# PR9017.net
KiCad netlist of a schematic drawn in EAGLE
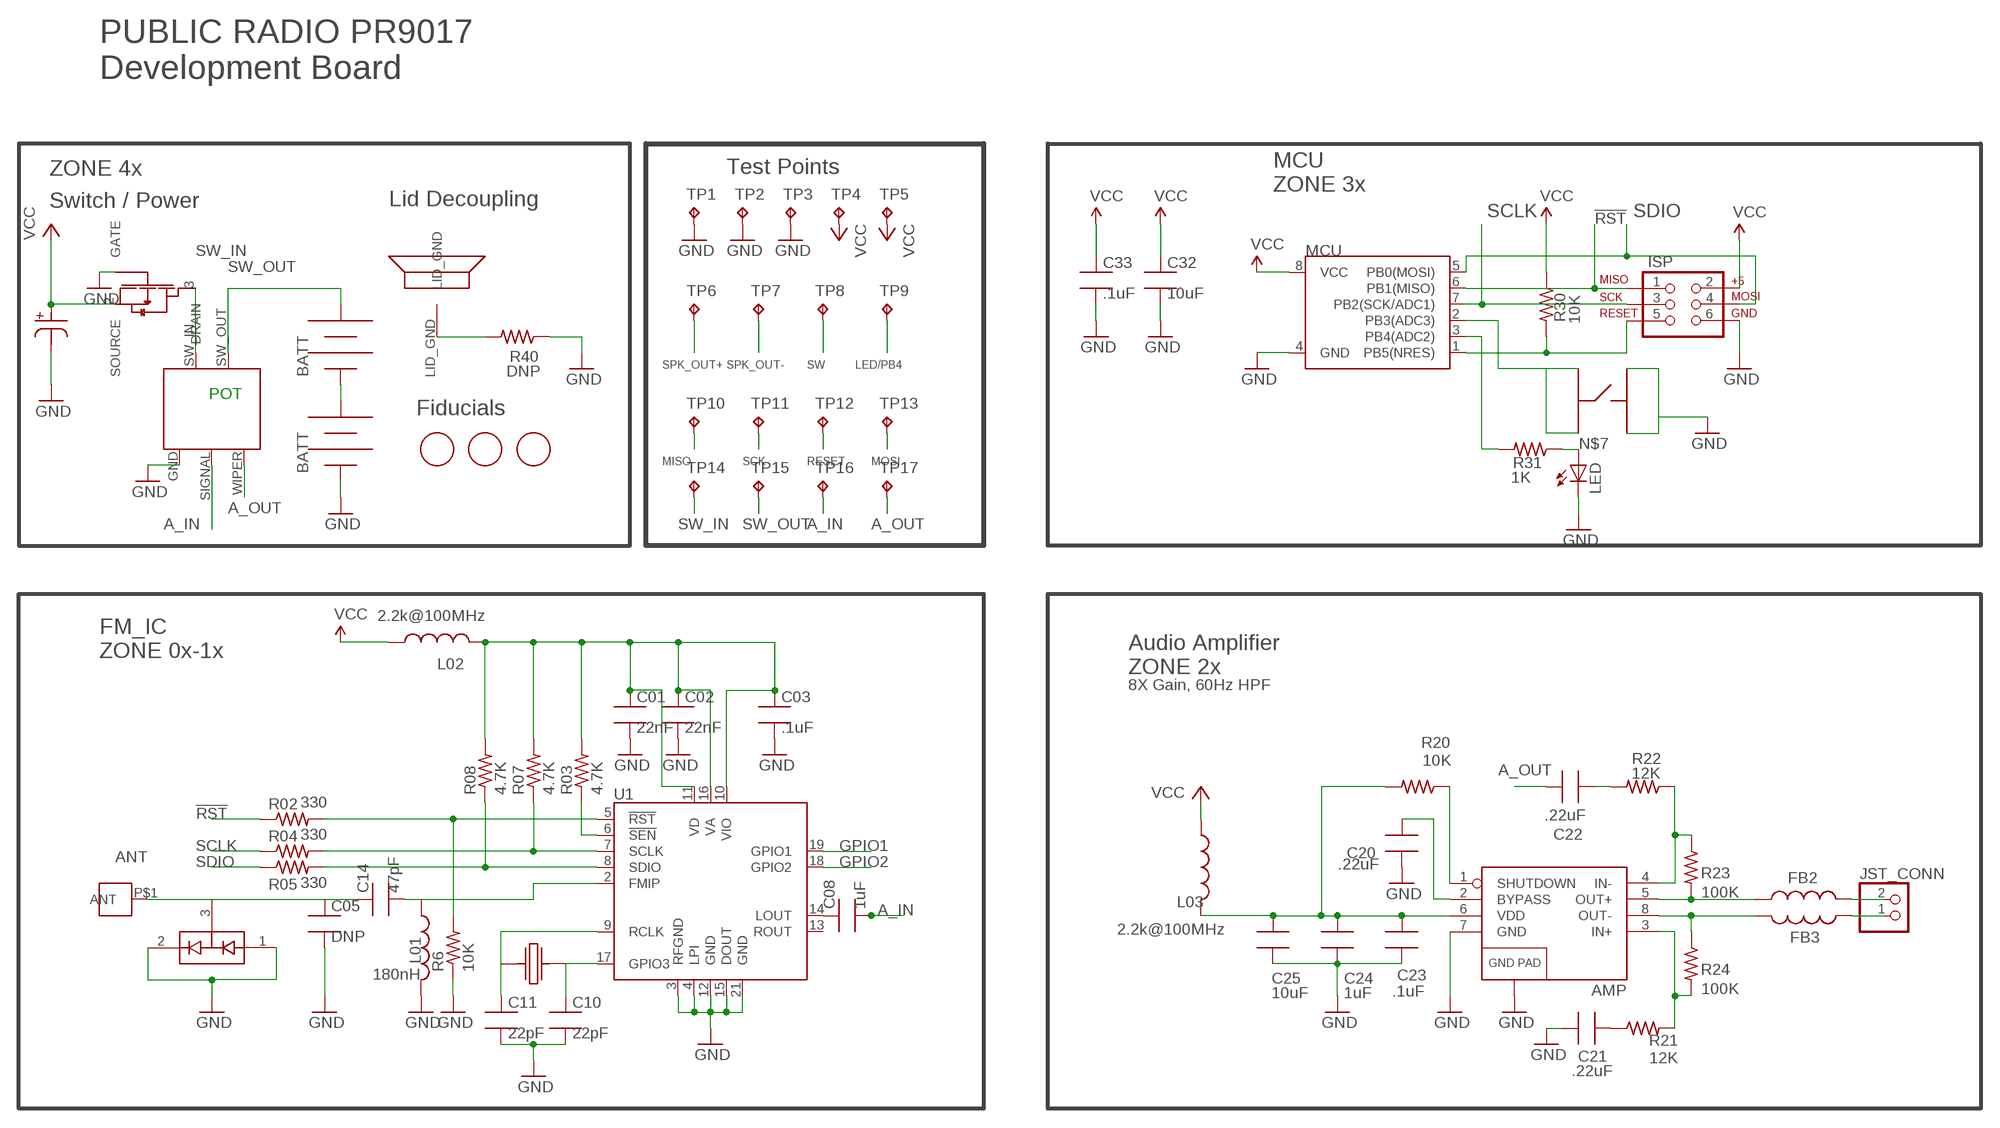
[diagram p0: schematic, sheet 1]

(export (version "E")
  (design (tool "Eeschema 10.0.6"))
  (components
    (comp (ref "AMP")
      (value "TPA6203A1")
      (footprint "eagle-import:8-MSOP")
      (libsource (lib "eagle-import") (part "TPA6203A1"))
    )
    (comp (ref "ANT_MOUNT")
      (value "DNP")
      (footprint "eagle-import:M3_BOLT_HOLE")
      (libsource (lib "eagle-import") (part "M3_SCREW_POST"))
    )
    (comp (ref "C01")
      (value "22nF")
      (footprint "eagle-import:0603_CPL")
      (fields
        (field (name "MFG_PN") "CL10B223KB8NNNC")
        (field (name "TOL") "10%")
        (field (name "VOLTAGE") "16V")
      )
      (libsource (lib "eagle-import") (part "C_SMT_0603_CPL"))
    )
    (comp (ref "C02")
      (value "22nF")
      (footprint "eagle-import:0603_CPL")
      (fields
        (field (name "MFG_PN") "CL10B223KB8NNNC")
        (field (name "TOL") "10%")
        (field (name "VOLTAGE") "16V")
      )
      (libsource (lib "eagle-import") (part "C_SMT_0603_CPL"))
    )
    (comp (ref "C03")
      (value ".1uF")
      (footprint "eagle-import:0603_CPL")
      (fields
        (field (name "MFG_PN") "CL05B104KO5NNNC")
        (field (name "TOL") "10%")
        (field (name "VOLTAGE") "16V")
      )
      (libsource (lib "eagle-import") (part "C_SMT_0603_CPL"))
    )
    (comp (ref "C05")
      (value "DNP")
      (footprint "eagle-import:0603_CPL")
      (fields (field (name "MFG_PN") "DNP") (field (name "TOL") "2%") (field (name "VOLTAGE") "50V"))
      (libsource (lib "eagle-import") (part "C_SMT_0603_CPL"))
    )
    (comp (ref "C08")
      (value "1uF")
      (footprint "eagle-import:0603_CPL")
      (fields
        (field (name "MFG_PN") "CL10B105KP8NNNC")
        (field (name "TOL") "10%")
        (field (name "VOLTAGE") "10V")
      )
      (libsource (lib "eagle-import") (part "C_SMT_0603_CPL"))
    )
    (comp (ref "C10")
      (value "22pF")
      (footprint "eagle-import:0603_CPL")
      (fields
        (field (name "MFG_PN") "C1608C0G1H220J080AA")
        (field (name "TOL") "5%")
        (field (name "VOLTAGE") "50V")
      )
      (libsource (lib "eagle-import") (part "C_SMT_0603_CPL"))
    )
    (comp (ref "C11")
      (value "22pF")
      (footprint "eagle-import:0603_CPL")
      (fields
        (field (name "MFG_PN") "C1608C0G1H220J080AA")
        (field (name "TOL") "5%")
        (field (name "VOLTAGE") "50V")
      )
      (libsource (lib "eagle-import") (part "C_SMT_0603_CPL"))
    )
    (comp (ref "C14")
      (value "47pF")
      (footprint "eagle-import:0603_CPL")
      (fields
        (field (name "MFG_PN") "CL10C470JB8NCNC")
        (field (name "TOL") "5%")
        (field (name "VOLTAGE") "50V")
      )
      (libsource (lib "eagle-import") (part "C_SMT_0603_CPL"))
    )
    (comp (ref "C20")
      (value ".22uF")
      (footprint "eagle-import:0603_CPL")
      (fields
        (field (name "MFG_PN") "C1608X7R1C224K080AC")
        (field (name "TOL") "10%")
        (field (name "VOLTAGE") "16V")
      )
      (libsource (lib "eagle-import") (part "C_SMT_0603_CPL"))
    )
    (comp (ref "C21")
      (value ".22uF")
      (footprint "eagle-import:0603_CPL")
      (fields
        (field (name "MFG_PN") "C1608X7R1C224K080AC")
        (field (name "TOL") "10%")
        (field (name "VOLTAGE") "16V")
      )
      (libsource (lib "eagle-import") (part "C_SMT_0603_CPL"))
    )
    (comp (ref "C22")
      (value ".22uF")
      (footprint "eagle-import:0603_CPL")
      (fields
        (field (name "MFG_PN") "C1608X7R1C224K080AC")
        (field (name "TOL") "10%")
        (field (name "VOLTAGE") "16V")
      )
      (libsource (lib "eagle-import") (part "C_SMT_0603_CPL"))
    )
    (comp (ref "C23")
      (value ".1uF")
      (footprint "eagle-import:0603_CPL")
      (fields
        (field (name "MFG_PN") "CL05B104KO5NNNC")
        (field (name "TOL") "10%")
        (field (name "VOLTAGE") "16V")
      )
      (libsource (lib "eagle-import") (part "C_SMT_0603_CPL"))
    )
    (comp (ref "C24")
      (value "1uF")
      (footprint "eagle-import:0603_CPL")
      (fields
        (field (name "MFG_PN") "CL10B105KP8NNNC")
        (field (name "TOL") "10%")
        (field (name "VOLTAGE") "10V")
      )
      (libsource (lib "eagle-import") (part "C_SMT_0603_CPL"))
    )
    (comp (ref "C25")
      (value "10uF")
      (footprint "eagle-import:0603_CPL")
      (fields
        (field (name "MFG_PN") "CL10A106MQ8NNNC")
        (field (name "TOL") "20%")
        (field (name "VOLTAGE") "6.3V")
      )
      (libsource (lib "eagle-import") (part "C_SMT_0603_CPL"))
    )
    (comp (ref "C32")
      (value "10uF")
      (footprint "eagle-import:0603_CPL")
      (fields
        (field (name "MFG_PN") "CL10A106MQ8NNNC")
        (field (name "TOL") "20%")
        (field (name "VOLTAGE") "6.3V")
      )
      (libsource (lib "eagle-import") (part "C_SMT_0603_CPL"))
    )
    (comp (ref "C33")
      (value ".1uF")
      (footprint "eagle-import:0603_CPL")
      (fields
        (field (name "MFG_PN") "CL05B104KO5NNNC")
        (field (name "TOL") "10%")
        (field (name "VOLTAGE") "16V")
      )
      (libsource (lib "eagle-import") (part "C_SMT_0603_CPL"))
    )
    (comp (ref "C40")
      (value "220uF")
      (footprint "eagle-import:NICHICON_UD_63")
      (fields (field (name "TOL") "20%") (field (name "VOLTAGE") "16V"))
      (libsource (lib "eagle-import") (part "NICHICON_SERIESUD"))
    )
    (comp (ref "D1")
      (value "BAV99")
      (footprint "eagle-import:SOT23_CPL")
      (fields (field (name "MFG_PN") "BAV99,215"))
      (libsource (lib "eagle-import") (part "BAV99"))
    )
    (comp (ref "FB2")
      (value "L_SMT_0805_ADAFRUIT")
      (footprint "eagle-import:0805_ADAFRUIT")
      (fields
        (field (name "CURRENT") "2A")
        (field (name "DCR") "45m")
        (field (name "MFG_PN") "HI0805R800R-10")
      )
      (libsource (lib "eagle-import") (part "L_SMT_0805_ADAFRUIT"))
    )
    (comp (ref "FB3")
      (value "L_SMT_0805_ADAFRUIT")
      (footprint "eagle-import:0805_ADAFRUIT")
      (fields
        (field (name "CURRENT") "2A")
        (field (name "DCR") "45m")
        (field (name "MFG_PN") "HI0805R800R-10")
      )
      (libsource (lib "eagle-import") (part "L_SMT_0805_ADAFRUIT"))
    )
    (comp (ref "FET1")
      (value "AO3435")
      (footprint "eagle-import:SOT23_CPL")
      (fields (field (name "MFG_PN") "AO3435"))
      (libsource (lib "eagle-import") (part "AO3435"))
    )
    (comp (ref "ISP")
      (value "AVR_SPI_PRG_6NS")
      (footprint "eagle-import:2X3-NS")
      (libsource (lib "eagle-import") (part "AVR_SPI_PRG_6NS"))
    )
    (comp (ref "JP5")
      (value "BK-92_MPD_AA_BATT_CLIP")
      (footprint "eagle-import:BK92_AA_BATT")
      (libsource (lib "eagle-import") (part "BK-92_MPD_AA_BATT_CLIP"))
    )
    (comp (ref "JP6")
      (value "BK-92_MPD_AA_BATT_CLIP")
      (footprint "eagle-import:BK92_AA_BATT")
      (libsource (lib "eagle-import") (part "BK-92_MPD_AA_BATT_CLIP"))
    )
    (comp (ref "JST_CONN")
      (value "JST_2PIN-SMT-RA")
      (footprint "eagle-import:JST-PH-2-SMT-RA")
      (libsource (lib "eagle-import") (part "JST_2PIN-SMT-RA"))
    )
    (comp (ref "L01")
      (value "180nH")
      (footprint "eagle-import:0805_ADAFRUIT")
      (fields
        (field (name "CURRENT") "400mA")
        (field (name "DCR") "640m")
        (field (name "MFG_PN") "AISC-0805-R18J-T")
        (field (name "TOL") "5%")
      )
      (libsource (lib "eagle-import") (part "L_SMT_0805_ADAFRUIT"))
    )
    (comp (ref "L02")
      (value "2.2k@100MHz")
      (footprint "eagle-import:0603_CPL")
      (fields
        (field (name "CURRENT") "150mA")
        (field (name "DCR") "2.3")
        (field (name "MFG_PN") "HZ0603A222R-10")
      )
      (libsource (lib "eagle-import") (part "L_SMT_0603_CPL"))
    )
    (comp (ref "L03")
      (value "2.2k@100MHz")
      (footprint "eagle-import:0603_CPL")
      (fields
        (field (name "CURRENT") "150mA")
        (field (name "DCR") "2.3")
        (field (name "MFG_PN") "HZ0603A222R-10")
      )
      (libsource (lib "eagle-import") (part "L_SMT_0603_CPL"))
    )
    (comp (ref "LED")
      (value "LED")
      (footprint "eagle-import:0603_CPL")
      (fields (field (name "MFG_PN") "LY R976-PS-36"))
      (libsource (lib "eagle-import") (part "LED"))
    )
    (comp (ref "MARK1")
      (value "FIDUCIAL")
      (footprint "eagle-import:FIDUCIAL_1MM")
      (libsource (lib "eagle-import") (part "FIDUCIAL"))
    )
    (comp (ref "MARK2")
      (value "FIDUCIAL")
      (footprint "eagle-import:FIDUCIAL_1MM")
      (libsource (lib "eagle-import") (part "FIDUCIAL"))
    )
    (comp (ref "MARK3")
      (value "FIDUCIAL")
      (footprint "eagle-import:FIDUCIAL_1MM")
      (libsource (lib "eagle-import") (part "FIDUCIAL"))
    )
    (comp (ref "MCU")
      (value "ATTINY45TINY45-20-SMT")
      (footprint "eagle-import:8-SOIC")
      (libsource (lib "eagle-import") (part "ATTINY45TINY45-20-SMT"))
    )
    (comp (ref "R1")
      (value "RV170SF_TAIWANA_POT_SW")
      (footprint "eagle-import:RV170SF_SW_POT")
      (libsource (lib "eagle-import") (part "RV170SF_TAIWANA_POT_SW"))
    )
    (comp (ref "R02")
      (value "330")
      (footprint "eagle-import:0603_CPL")
      (fields (field (name "MFG_PN") "MCR03ERTJ331") (field (name "POWER") "1/10W") (field (name "TOL") "5%"))
      (libsource (lib "eagle-import") (part "R_SMT_R0603_CPL"))
    )
    (comp (ref "R03")
      (value "4.7K")
      (footprint "eagle-import:0603_CPL")
      (fields
        (field (name "MFG_PN") "ERJ-3EKF4701V")
        (field (name "POWER") "1/10W")
        (field (name "TOL") "1%")
      )
      (libsource (lib "eagle-import") (part "R_SMT_R0603_CPL"))
    )
    (comp (ref "R04")
      (value "330")
      (footprint "eagle-import:0603_CPL")
      (fields (field (name "MFG_PN") "MCR03ERTJ331") (field (name "POWER") "1/10W") (field (name "TOL") "5%"))
      (libsource (lib "eagle-import") (part "R_SMT_R0603_CPL"))
    )
    (comp (ref "R05")
      (value "330")
      (footprint "eagle-import:0603_CPL")
      (fields (field (name "MFG_PN") "MCR03ERTJ331") (field (name "POWER") "1/10W") (field (name "TOL") "5%"))
      (libsource (lib "eagle-import") (part "R_SMT_R0603_CPL"))
    )
    (comp (ref "R6")
      (value "10K")
      (footprint "eagle-import:0603_CPL")
      (fields
        (field (name "MFG_PN") "ERJ-3GEYJ103V")
        (field (name "POWER") "1/10W")
        (field (name "TOL") "5%")
      )
      (libsource (lib "eagle-import") (part "R_SMT_R0603_CPL"))
    )
    (comp (ref "R07")
      (value "4.7K")
      (footprint "eagle-import:0603_CPL")
      (fields
        (field (name "MFG_PN") "ERJ-3EKF4701V")
        (field (name "POWER") "1/10W")
        (field (name "TOL") "1%")
      )
      (libsource (lib "eagle-import") (part "R_SMT_R0603_CPL"))
    )
    (comp (ref "R08")
      (value "4.7K")
      (footprint "eagle-import:0603_CPL")
      (fields
        (field (name "MFG_PN") "ERJ-3EKF4701V")
        (field (name "POWER") "1/10W")
        (field (name "TOL") "1%")
      )
      (libsource (lib "eagle-import") (part "R_SMT_R0603_CPL"))
    )
    (comp (ref "R20")
      (value "10K")
      (footprint "eagle-import:0603_CPL")
      (fields
        (field (name "MFG_PN") "ERJ-3GEYJ103V")
        (field (name "POWER") "1/10W")
        (field (name "TOL") "5%")
      )
      (libsource (lib "eagle-import") (part "R_SMT_R0603_CPL"))
    )
    (comp (ref "R21")
      (value "12K")
      (footprint "eagle-import:0603_CPL")
      (fields
        (field (name "MFG_PN") "RMCF0603FT12K0")
        (field (name "POWER") "1/10W")
        (field (name "TOL") "1%")
      )
      (libsource (lib "eagle-import") (part "R_SMT_R0603_CPL"))
    )
    (comp (ref "R22")
      (value "12K")
      (footprint "eagle-import:0603_CPL")
      (fields
        (field (name "MFG_PN") "RMCF0603FT12K0")
        (field (name "POWER") "1/10W")
        (field (name "TOL") "1%")
      )
      (libsource (lib "eagle-import") (part "R_SMT_R0603_CPL"))
    )
    (comp (ref "R23")
      (value "100K")
      (footprint "eagle-import:0603_CPL")
      (fields
        (field (name "MFG_PN") "RMCF0603FT100K")
        (field (name "POWER") "1/10W")
        (field (name "TOL") "1%")
      )
      (libsource (lib "eagle-import") (part "R_SMT_R0603_CPL"))
    )
    (comp (ref "R24")
      (value "100K")
      (footprint "eagle-import:0603_CPL")
      (fields
        (field (name "MFG_PN") "RMCF0603FT100K")
        (field (name "POWER") "1/10W")
        (field (name "TOL") "1%")
      )
      (libsource (lib "eagle-import") (part "R_SMT_R0603_CPL"))
    )
    (comp (ref "R30")
      (value "10K")
      (footprint "eagle-import:0603_CPL")
      (fields
        (field (name "MFG_PN") "ERJ-3GEYJ103V")
        (field (name "POWER") "1/10W")
        (field (name "TOL") "5%")
      )
      (libsource (lib "eagle-import") (part "R_SMT_R0603_CPL"))
    )
    (comp (ref "R31")
      (value "1K")
      (footprint "eagle-import:0603_CPL")
      (fields
        (field (name "MFG_PN") "ERJ-3EKF1001V")
        (field (name "POWER") "1/10W")
        (field (name "TOL") "1%")
      )
      (libsource (lib "eagle-import") (part "R_SMT_R0603_CPL"))
    )
    (comp (ref "R40")
      (value "DNP")
      (footprint "eagle-import:0603_CPL")
      (fields (field (name "MFG_PN") "ERJ-3GEY0R00V"))
      (libsource (lib "eagle-import") (part "R_SMT_R0603_CPL"))
    )
    (comp (ref "SPKR_PLACE")
      (value "DNP")
      (footprint "eagle-import:PR2023_SPKR_PLACE")
      (libsource (lib "eagle-import") (part "PR2023_SPKR"))
    )
    (comp (ref "SW1")
      (value "C&K_PTS645")
      (footprint "eagle-import:C&K_PTS645_SMT")
      (libsource (lib "eagle-import") (part "C&K_PTS645"))
    )
    (comp (ref "TP1")
      (value "TPTP20R")
      (footprint "eagle-import:TP20R")
      (libsource (lib "eagle-import") (part "TPTP20R"))
    )
    (comp (ref "TP2")
      (value "TPTP20R")
      (footprint "eagle-import:TP20R")
      (libsource (lib "eagle-import") (part "TPTP20R"))
    )
    (comp (ref "TP3")
      (value "TPTP20R")
      (footprint "eagle-import:TP20R")
      (libsource (lib "eagle-import") (part "TPTP20R"))
    )
    (comp (ref "TP4")
      (value "TPTP20R")
      (footprint "eagle-import:TP20R")
      (libsource (lib "eagle-import") (part "TPTP20R"))
    )
    (comp (ref "TP5")
      (value "TPTP20R")
      (footprint "eagle-import:TP20R")
      (libsource (lib "eagle-import") (part "TPTP20R"))
    )
    (comp (ref "TP6")
      (value "TPTP20R")
      (footprint "eagle-import:TP20R")
      (libsource (lib "eagle-import") (part "TPTP20R"))
    )
    (comp (ref "TP7")
      (value "TPTP20R")
      (footprint "eagle-import:TP20R")
      (libsource (lib "eagle-import") (part "TPTP20R"))
    )
    (comp (ref "TP8")
      (value "TPTP20R")
      (footprint "eagle-import:TP20R")
      (libsource (lib "eagle-import") (part "TPTP20R"))
    )
    (comp (ref "TP9")
      (value "TPTP20R")
      (footprint "eagle-import:TP20R")
      (libsource (lib "eagle-import") (part "TPTP20R"))
    )
    (comp (ref "TP10")
      (value "TPTP20R")
      (footprint "eagle-import:TP20R")
      (libsource (lib "eagle-import") (part "TPTP20R"))
    )
    (comp (ref "TP11")
      (value "TPTP20R")
      (footprint "eagle-import:TP20R")
      (libsource (lib "eagle-import") (part "TPTP20R"))
    )
    (comp (ref "TP12")
      (value "TPTP20R")
      (footprint "eagle-import:TP20R")
      (libsource (lib "eagle-import") (part "TPTP20R"))
    )
    (comp (ref "TP13")
      (value "TPTP20R")
      (footprint "eagle-import:TP20R")
      (libsource (lib "eagle-import") (part "TPTP20R"))
    )
    (comp (ref "TP14")
      (value "TPTP20R")
      (footprint "eagle-import:TP20R")
      (libsource (lib "eagle-import") (part "TPTP20R"))
    )
    (comp (ref "TP15")
      (value "TPTP20R")
      (footprint "eagle-import:TP20R")
      (libsource (lib "eagle-import") (part "TPTP20R"))
    )
    (comp (ref "TP16")
      (value "TPTP20R")
      (footprint "eagle-import:TP20R")
      (libsource (lib "eagle-import") (part "TPTP20R"))
    )
    (comp (ref "TP17")
      (value "TPTP20R")
      (footprint "eagle-import:TP20R")
      (libsource (lib "eagle-import") (part "TPTP20R"))
    )
    (comp (ref "U1")
      (value "SI4702-C19-GMR")
      (footprint "eagle-import:SI470X_20_QFN")
      (libsource (lib "eagle-import") (part "SI4702-C19-GMR"))
    )
    (comp (ref "X1")
      (value "ABS25XTAL")
      (footprint "eagle-import:4-SOJ")
      (libsource (lib "eagle-import") (part "ABS25XTAL"))
    )
  )
  (nets
    (net (code "1") (name "/ANT") (class "Default")
      (node (ref "ANT_MOUNT") (pin "P$1") (pinfunction "ANT_P$1") (pintype "bidirectional"))
      (node (ref "C05") (pin "1") (pinfunction "1_1") (pintype "passive"))
      (node (ref "C14") (pin "1") (pinfunction "1_1") (pintype "passive"))
      (node (ref "D1") (pin "3") (pinfunction "COM_3") (pintype "bidirectional"))
    )
    (net (code "2") (name "/A_IN") (class "Default")
      (node (ref "C08") (pin "2") (pinfunction "2_2") (pintype "passive"))
      (node (ref "R1") (pin "SIGNAL") (pinfunction "SIGNAL_SIGNAL") (pintype "bidirectional"))
      (node (ref "TP16") (pin "TP") (pinfunction "TP_TP") (pintype "input"))
    )
    (net (code "3") (name "/A_OUT") (class "Default")
      (node (ref "C22") (pin "2") (pinfunction "2_2") (pintype "passive"))
      (node (ref "R1") (pin "WIPER") (pinfunction "WIPER_WIPER") (pintype "bidirectional"))
      (node (ref "TP17") (pin "TP") (pinfunction "TP_TP") (pintype "input"))
    )
    (net (code "4") (name "/GPIO1") (class "Default")
      (node (ref "U1") (pin "19") (pinfunction "GPIO1_19") (pintype "bidirectional"))
    )
    (net (code "5") (name "/GPIO2") (class "Default")
      (node (ref "U1") (pin "18") (pinfunction "GPIO2_18") (pintype "bidirectional"))
    )
    (net (code "6") (name "/LED{slash}PB4") (class "Default")
      (node (ref "MCU") (pin "3") (pinfunction "PB4(ADC2)_3") (pintype "bidirectional"))
      (node (ref "R31") (pin "2") (pinfunction "2_2") (pintype "passive"))
      (node (ref "TP9") (pin "TP") (pinfunction "TP_TP") (pintype "input"))
    )
    (net (code "7") (name "/N$7") (class "Default")
      (node (ref "LED") (pin "1") (pinfunction "A_1") (pintype "passive"))
      (node (ref "R31") (pin "1") (pinfunction "1_1") (pintype "passive"))
    )
    (net (code "8") (name "/RESET") (class "Default")
      (node (ref "ISP") (pin "5") (pinfunction "5_5") (pintype "passive"))
      (node (ref "MCU") (pin "1") (pinfunction "PB5(NRES)_1") (pintype "bidirectional"))
      (node (ref "R30") (pin "2") (pinfunction "2_2") (pintype "passive"))
      (node (ref "TP12") (pin "TP") (pinfunction "TP_TP") (pintype "input"))
    )
    (net (code "9") (name "/SCLK") (class "Default")
      (node (ref "ISP") (pin "3") (pinfunction "3_3") (pintype "passive"))
      (node (ref "MCU") (pin "7") (pinfunction "PB2(SCK/ADC1)_7") (pintype "bidirectional"))
      (node (ref "R04") (pin "1") (pinfunction "1_1") (pintype "passive"))
      (node (ref "TP11") (pin "TP") (pinfunction "TP_TP") (pintype "input"))
    )
    (net (code "10") (name "/SDIO") (class "Default")
      (node (ref "ISP") (pin "4") (pinfunction "4_4") (pintype "passive"))
      (node (ref "MCU") (pin "5") (pinfunction "PB0(MOSI)_5") (pintype "bidirectional"))
      (node (ref "R05") (pin "1") (pinfunction "1_1") (pintype "passive"))
      (node (ref "TP13") (pin "TP") (pinfunction "TP_TP") (pintype "input"))
    )
    (net (code "11") (name "/SPK_OUT+") (class "Default")
      (node (ref "FB2") (pin "2") (pinfunction "2_2") (pintype "passive"))
      (node (ref "JST_CONN") (pin "2") (pinfunction "1_2") (pintype "passive"))
      (node (ref "TP6") (pin "TP") (pinfunction "TP_TP") (pintype "input"))
    )
    (net (code "12") (name "/SPK_OUT-") (class "Default")
      (node (ref "FB3") (pin "1") (pinfunction "1_1") (pintype "passive"))
      (node (ref "JST_CONN") (pin "1") (pinfunction "2_1") (pintype "passive"))
      (node (ref "TP7") (pin "TP") (pinfunction "TP_TP") (pintype "input"))
    )
    (net (code "13") (name "/SW") (class "Default")
      (node (ref "MCU") (pin "2") (pinfunction "PB3(ADC3)_2") (pintype "bidirectional"))
      (node (ref "SW1") (pin "P$3") (pinfunction "P$3_P$3") (pintype "bidirectional"))
      (node (ref "SW1") (pin "P$4") (pinfunction "P$4_P$4") (pintype "bidirectional"))
      (node (ref "TP8") (pin "TP") (pinfunction "TP_TP") (pintype "input"))
    )
    (net (code "14") (name "/SW_IN") (class "Default")
      (node (ref "FET1") (pin "3") (pinfunction "DRAIN_3") (pintype "bidirectional"))
      (node (ref "R1") (pin "SW_IN") (pinfunction "SW_IN_SW_IN") (pintype "bidirectional"))
      (node (ref "TP14") (pin "TP") (pinfunction "TP_TP") (pintype "input"))
    )
    (net (code "15") (name "/SW_OUT") (class "Default")
      (node (ref "JP5") (pin "POS") (pinfunction "POS_POS") (pintype "bidirectional"))
      (node (ref "JP5") (pin "POS@2") (pinfunction "POS_POS@2") (pintype "bidirectional"))
      (node (ref "R1") (pin "SW_OUT") (pinfunction "SW_OUT_SW_OUT") (pintype "bidirectional"))
      (node (ref "TP15") (pin "TP") (pinfunction "TP_TP") (pintype "input"))
    )
    (net (code "16") (name "/~{RST}") (class "Default")
      (node (ref "ISP") (pin "1") (pinfunction "1_1") (pintype "passive"))
      (node (ref "MCU") (pin "6") (pinfunction "PB1(MISO)_6") (pintype "bidirectional"))
      (node (ref "R02") (pin "1") (pinfunction "1_1") (pintype "passive"))
      (node (ref "TP10") (pin "TP") (pinfunction "TP_TP") (pintype "input"))
    )
    (net (code "17") (name "GND") (class "Default")
      (node (ref "AMP") (pin "7") (pinfunction "GND_7") (pintype "power_in"))
      (node (ref "AMP") (pin "9") (pinfunction "GND_9") (pintype "power_in"))
      (node (ref "C01") (pin "2") (pinfunction "2_2") (pintype "passive"))
      (node (ref "C02") (pin "2") (pinfunction "2_2") (pintype "passive"))
      (node (ref "C03") (pin "2") (pinfunction "2_2") (pintype "passive"))
      (node (ref "C05") (pin "2") (pinfunction "2_2") (pintype "passive"))
      (node (ref "C10") (pin "2") (pinfunction "2_2") (pintype "passive"))
      (node (ref "C11") (pin "2") (pinfunction "2_2") (pintype "passive"))
      (node (ref "C20") (pin "1") (pinfunction "1_1") (pintype "passive"))
      (node (ref "C21") (pin "1") (pinfunction "1_1") (pintype "passive"))
      (node (ref "C23") (pin "2") (pinfunction "2_2") (pintype "passive"))
      (node (ref "C24") (pin "2") (pinfunction "2_2") (pintype "passive"))
      (node (ref "C25") (pin "2") (pinfunction "2_2") (pintype "passive"))
      (node (ref "C32") (pin "2") (pinfunction "2_2") (pintype "passive"))
      (node (ref "C33") (pin "2") (pinfunction "2_2") (pintype "passive"))
      (node (ref "C40") (pin "P$2") (pinfunction "P$2_P$2") (pintype "bidirectional"))
      (node (ref "D1") (pin "1") (pinfunction "A1_1") (pintype "bidirectional"))
      (node (ref "D1") (pin "2") (pinfunction "C2_2") (pintype "bidirectional"))
      (node (ref "FET1") (pin "1") (pinfunction "GATE_1") (pintype "bidirectional"))
      (node (ref "ISP") (pin "6") (pinfunction "6_6") (pintype "passive"))
      (node (ref "JP6") (pin "NEG") (pinfunction "NEG_NEG") (pintype "bidirectional"))
      (node (ref "JP6") (pin "NEG@2") (pinfunction "NEG_NEG@2") (pintype "bidirectional"))
      (node (ref "L01") (pin "2") (pinfunction "2_2") (pintype "passive"))
      (node (ref "LED") (pin "2") (pinfunction "C_2") (pintype "passive"))
      (node (ref "MCU") (pin "4") (pinfunction "GND_4") (pintype "bidirectional"))
      (node (ref "R1") (pin "GND") (pinfunction "GND_GND") (pintype "bidirectional"))
      (node (ref "R40") (pin "1") (pinfunction "1_1") (pintype "passive"))
      (node (ref "R6") (pin "1") (pinfunction "1_1") (pintype "passive"))
      (node (ref "SW1") (pin "P$1") (pinfunction "P$1_P$1") (pintype "bidirectional"))
      (node (ref "SW1") (pin "P$2") (pinfunction "P$2_P$2") (pintype "bidirectional"))
      (node (ref "TP1") (pin "TP") (pinfunction "TP_TP") (pintype "input"))
      (node (ref "TP2") (pin "TP") (pinfunction "TP_TP") (pintype "input"))
      (node (ref "TP3") (pin "TP") (pinfunction "TP_TP") (pintype "input"))
      (node (ref "U1") (pin "12") (pinfunction "GND_12") (pintype "bidirectional"))
      (node (ref "U1") (pin "15") (pinfunction "DOUT_15") (pintype "bidirectional"))
      (node (ref "U1") (pin "21") (pinfunction "GND_21") (pintype "bidirectional"))
      (node (ref "U1") (pin "3") (pinfunction "RFGND_3") (pintype "bidirectional"))
      (node (ref "U1") (pin "4") (pinfunction "LPI_4") (pintype "bidirectional"))
    )
    (net (code "18") (name "Net-(AMP-BYPASS)") (class "Default")
      (node (ref "AMP") (pin "2") (pinfunction "BYPASS_2") (pintype "bidirectional"))
      (node (ref "C20") (pin "2") (pinfunction "2_2") (pintype "passive"))
    )
    (net (code "19") (name "Net-(AMP-IN+)") (class "Default")
      (node (ref "AMP") (pin "3") (pinfunction "IN+_3") (pintype "bidirectional"))
      (node (ref "R21") (pin "2") (pinfunction "2_2") (pintype "passive"))
      (node (ref "R24") (pin "2") (pinfunction "2_2") (pintype "passive"))
    )
    (net (code "20") (name "Net-(AMP-IN-)") (class "Default")
      (node (ref "AMP") (pin "4") (pinfunction "IN-_4") (pintype "bidirectional"))
      (node (ref "R22") (pin "1") (pinfunction "1_1") (pintype "passive"))
      (node (ref "R23") (pin "1") (pinfunction "1_1") (pintype "passive"))
    )
    (net (code "21") (name "Net-(AMP-OUT+)") (class "Default")
      (node (ref "AMP") (pin "5") (pinfunction "OUT+_5") (pintype "bidirectional"))
      (node (ref "FB2") (pin "1") (pinfunction "1_1") (pintype "passive"))
      (node (ref "R23") (pin "2") (pinfunction "2_2") (pintype "passive"))
    )
    (net (code "22") (name "Net-(AMP-OUT-)") (class "Default")
      (node (ref "AMP") (pin "8") (pinfunction "OUT-_8") (pintype "bidirectional"))
      (node (ref "FB3") (pin "2") (pinfunction "2_2") (pintype "passive"))
      (node (ref "R24") (pin "1") (pinfunction "1_1") (pintype "passive"))
    )
    (net (code "23") (name "Net-(AMP-SHUTDOWN)") (class "Default")
      (node (ref "AMP") (pin "1") (pinfunction "SHUTDOWN_1") (pintype "input"))
      (node (ref "R20") (pin "1") (pinfunction "1_1") (pintype "passive"))
    )
    (net (code "24") (name "Net-(AMP-VDD)") (class "Default")
      (node (ref "AMP") (pin "6") (pinfunction "VDD_6") (pintype "power_in"))
      (node (ref "C23") (pin "1") (pinfunction "1_1") (pintype "passive"))
      (node (ref "C24") (pin "1") (pinfunction "1_1") (pintype "passive"))
      (node (ref "C25") (pin "1") (pinfunction "1_1") (pintype "passive"))
      (node (ref "L03") (pin "2") (pinfunction "2_2") (pintype "passive"))
      (node (ref "R20") (pin "2") (pinfunction "2_2") (pintype "passive"))
    )
    (net (code "25") (name "Net-(C21-Pad2)") (class "Default")
      (node (ref "C21") (pin "2") (pinfunction "2_2") (pintype "passive"))
      (node (ref "R21") (pin "1") (pinfunction "1_1") (pintype "passive"))
    )
    (net (code "26") (name "Net-(C22-Pad1)") (class "Default")
      (node (ref "C22") (pin "1") (pinfunction "1_1") (pintype "passive"))
      (node (ref "R22") (pin "2") (pinfunction "2_2") (pintype "passive"))
    )
    (net (code "27") (name "Net-(JP5-NEG-PadNEG@2)") (class "Default")
      (node (ref "JP5") (pin "NEG") (pinfunction "NEG_NEG") (pintype "bidirectional"))
      (node (ref "JP5") (pin "NEG@2") (pinfunction "NEG_NEG@2") (pintype "bidirectional"))
      (node (ref "JP6") (pin "POS") (pinfunction "POS_POS") (pintype "bidirectional"))
      (node (ref "JP6") (pin "POS@2") (pinfunction "POS_POS@2") (pintype "bidirectional"))
    )
    (net (code "28") (name "Net-(R40-Pad2)") (class "Default")
      (node (ref "R40") (pin "2") (pinfunction "2_2") (pintype "passive"))
      (node (ref "SPKR_PLACE") (pin "LID_GND") (pinfunction "LID_GND_LID_GND") (pintype "bidirectional"))
    )
    (net (code "29") (name "Net-(U1-FMIP)") (class "Default")
      (node (ref "C14") (pin "2") (pinfunction "2_2") (pintype "passive"))
      (node (ref "L01") (pin "1") (pinfunction "1_1") (pintype "passive"))
      (node (ref "U1") (pin "2") (pinfunction "FMIP_2") (pintype "bidirectional"))
    )
    (net (code "30") (name "Net-(U1-GPIO3)") (class "Default")
      (node (ref "C10") (pin "1") (pinfunction "1_1") (pintype "passive"))
      (node (ref "U1") (pin "17") (pinfunction "GPIO3_17") (pintype "bidirectional"))
      (node (ref "X1") (pin "P$4") (pinfunction "P$4_P$4") (pintype "bidirectional"))
    )
    (net (code "31") (name "Net-(U1-LOUT)") (class "Default")
      (node (ref "C08") (pin "1") (pinfunction "1_1") (pintype "passive"))
      (node (ref "U1") (pin "14") (pinfunction "LOUT_14") (pintype "bidirectional"))
    )
    (net (code "32") (name "Net-(U1-RCLK)") (class "Default")
      (node (ref "C11") (pin "1") (pinfunction "1_1") (pintype "passive"))
      (node (ref "U1") (pin "9") (pinfunction "RCLK_9") (pintype "bidirectional"))
      (node (ref "X1") (pin "P$1") (pinfunction "P$1_P$1") (pintype "bidirectional"))
    )
    (net (code "33") (name "Net-(U1-SCLK)") (class "Default")
      (node (ref "R04") (pin "2") (pinfunction "2_2") (pintype "passive"))
      (node (ref "R07") (pin "1") (pinfunction "1_1") (pintype "passive"))
      (node (ref "U1") (pin "7") (pinfunction "SCLK_7") (pintype "bidirectional"))
    )
    (net (code "34") (name "Net-(U1-SDIO)") (class "Default")
      (node (ref "R05") (pin "2") (pinfunction "2_2") (pintype "passive"))
      (node (ref "R08") (pin "1") (pinfunction "1_1") (pintype "passive"))
      (node (ref "U1") (pin "8") (pinfunction "SDIO_8") (pintype "bidirectional"))
    )
    (net (code "35") (name "Net-(U1-VA)") (class "Default")
      (node (ref "C01") (pin "1") (pinfunction "1_1") (pintype "passive"))
      (node (ref "C02") (pin "1") (pinfunction "1_1") (pintype "passive"))
      (node (ref "C03") (pin "1") (pinfunction "1_1") (pintype "passive"))
      (node (ref "L02") (pin "2") (pinfunction "2_2") (pintype "passive"))
      (node (ref "R03") (pin "2") (pinfunction "2_2") (pintype "passive"))
      (node (ref "R07") (pin "2") (pinfunction "2_2") (pintype "passive"))
      (node (ref "R08") (pin "2") (pinfunction "2_2") (pintype "passive"))
      (node (ref "U1") (pin "10") (pinfunction "VIO_10") (pintype "bidirectional"))
      (node (ref "U1") (pin "11") (pinfunction "VD_11") (pintype "bidirectional"))
      (node (ref "U1") (pin "16") (pinfunction "VA_16") (pintype "bidirectional"))
    )
    (net (code "36") (name "Net-(U1-~{RST})") (class "Default")
      (node (ref "R02") (pin "2") (pinfunction "2_2") (pintype "passive"))
      (node (ref "R6") (pin "2") (pinfunction "2_2") (pintype "passive"))
      (node (ref "U1") (pin "5") (pinfunction "~{RST}_5") (pintype "bidirectional"))
    )
    (net (code "37") (name "Net-(U1-~{SEN})") (class "Default")
      (node (ref "R03") (pin "1") (pinfunction "1_1") (pintype "passive"))
      (node (ref "U1") (pin "6") (pinfunction "~{SEN}_6") (pintype "bidirectional"))
    )
    (net (code "38") (name "VCC") (class "Default")
      (node (ref "C32") (pin "1") (pinfunction "1_1") (pintype "passive"))
      (node (ref "C33") (pin "1") (pinfunction "1_1") (pintype "passive"))
      (node (ref "C40") (pin "P$1") (pinfunction "P$1_P$1") (pintype "bidirectional"))
      (node (ref "FET1") (pin "2") (pinfunction "SOURCE_2") (pintype "bidirectional"))
      (node (ref "ISP") (pin "2") (pinfunction "2_2") (pintype "passive"))
      (node (ref "L02") (pin "1") (pinfunction "1_1") (pintype "passive"))
      (node (ref "L03") (pin "1") (pinfunction "1_1") (pintype "passive"))
      (node (ref "MCU") (pin "8") (pinfunction "VCC_8") (pintype "bidirectional"))
      (node (ref "R30") (pin "1") (pinfunction "1_1") (pintype "passive"))
      (node (ref "TP4") (pin "TP") (pinfunction "TP_TP") (pintype "input"))
      (node (ref "TP5") (pin "TP") (pinfunction "TP_TP") (pintype "input"))
    )
    (net (code "39") (name "unconnected-(U1-ROUT-Pad13)") (class "Default")
      (node (ref "U1") (pin "13") (pinfunction "ROUT_13") (pintype "bidirectional"))
    )
  )
)
